# open-usb-can-2021.net
KiCad netlist of a schematic drawn in EAGLE
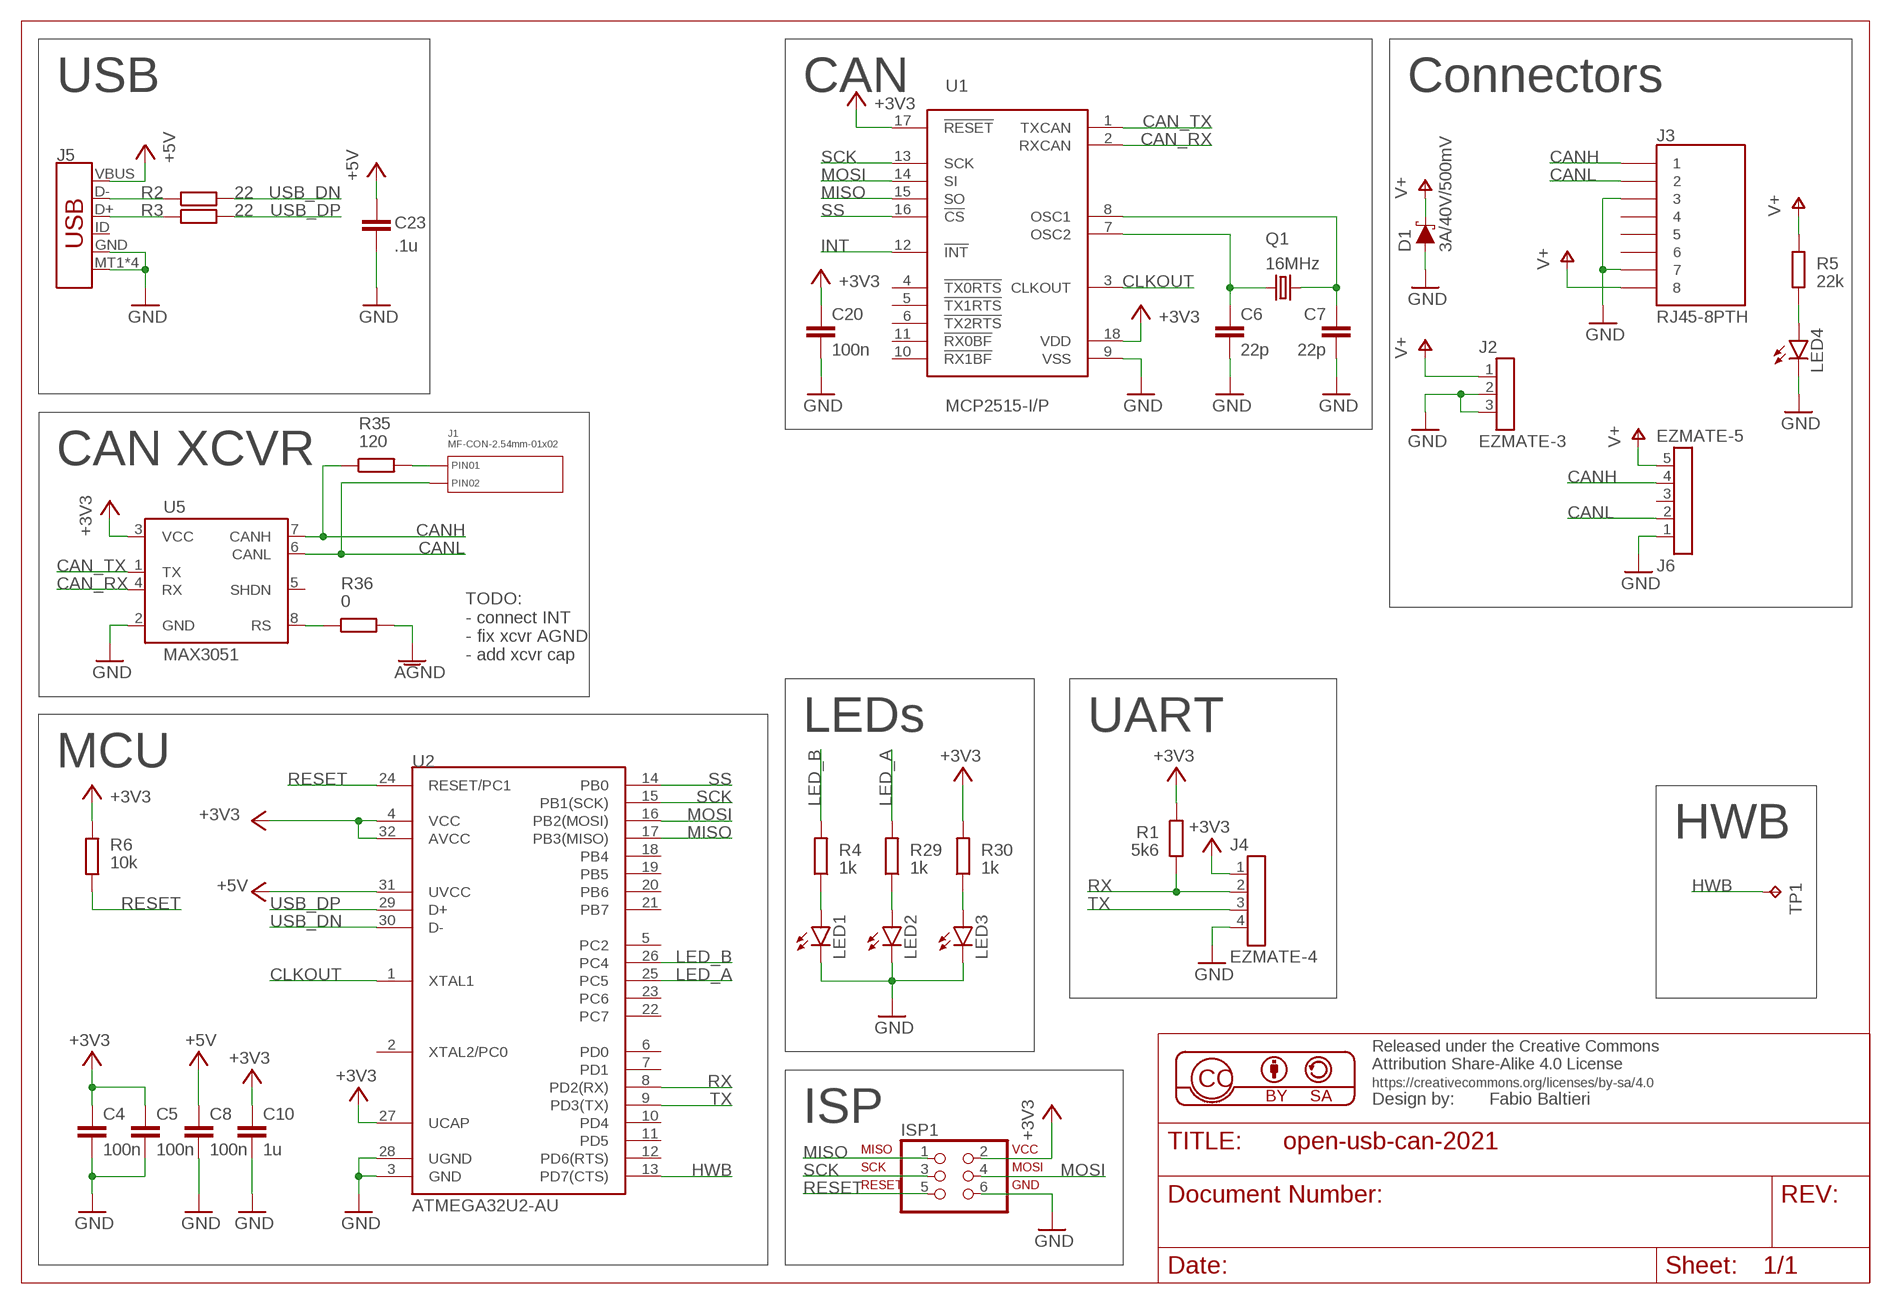
[diagram p0: schematic, sheet 1]

(export (version "E")
  (design (tool "Eeschema 10.0.6"))
  (components
    (comp (ref "C4")
      (value "100n")
      (footprint "eagle-import:0402")
      (libsource (lib "eagle-import") (part "C0402"))
    )
    (comp (ref "C5")
      (value "100n")
      (footprint "eagle-import:0402")
      (libsource (lib "eagle-import") (part "C0402"))
    )
    (comp (ref "C6")
      (value "22p")
      (footprint "eagle-import:C0805")
      (libsource (lib "eagle-import") (part "C-EUC0805"))
    )
    (comp (ref "C7")
      (value "22p")
      (footprint "eagle-import:C0805")
      (libsource (lib "eagle-import") (part "C-EUC0805"))
    )
    (comp (ref "C8")
      (value "100n")
      (footprint "eagle-import:0402")
      (libsource (lib "eagle-import") (part "C0402"))
    )
    (comp (ref "C10")
      (value "1u")
      (footprint "eagle-import:0603")
      (libsource (lib "eagle-import") (part "C0603"))
    )
    (comp (ref "C20")
      (value "100n")
      (footprint "eagle-import:0402")
      (libsource (lib "eagle-import") (part "C0402"))
    )
    (comp (ref "C23")
      (value ".1u")
      (footprint "eagle-import:0603")
      (libsource (lib "eagle-import") (part "C0603"))
    )
    (comp (ref "D1")
      (value "3A/40V/500mV")
      (footprint "eagle-import:SMA-DIODE")
      (libsource (lib "eagle-import") (part "DIODE-SCHOTTKY-B340A"))
    )
    (comp (ref "ISP1")
      (value "ISP-AVR910TP")
      (footprint "eagle-import:2X03_TP")
      (libsource (lib "eagle-import") (part "ISP-AVR910TP"))
    )
    (comp (ref "J1")
      (value "MF-CON-2.54mm-01x02")
      (footprint "eagle-import:PTH_2.54MM_01X02")
      (fields (field (name "HOUSEPART") "YES"))
      (libsource (lib "eagle-import") (part "CON_01X02_PTH_2.54MM"))
    )
    (comp (ref "J2")
      (value "EZMATE-3")
      (footprint "eagle-import:EZMATE-3")
      (libsource (lib "eagle-import") (part "EZMATE-3"))
    )
    (comp (ref "J3")
      (value "RJ45-8PTH")
      (footprint "eagle-import:RJ45-8")
      (libsource (lib "eagle-import") (part "RJ45-8PTH"))
    )
    (comp (ref "J4")
      (value "EZMATE-4")
      (footprint "eagle-import:EZMATE-4")
      (libsource (lib "eagle-import") (part "EZMATE-4"))
    )
    (comp (ref "J5")
      (value "USB_MICRO-B_SMT")
      (footprint "eagle-import:USB-MICROB")
      (libsource (lib "eagle-import") (part "USB_MICRO-B_SMT"))
    )
    (comp (ref "J6")
      (value "EZMATE-5")
      (footprint "eagle-import:EZMATE-5")
      (libsource (lib "eagle-import") (part "EZMATE-5"))
    )
    (comp (ref "LED1")
      (value "LEDCHIPLED_0603")
      (footprint "eagle-import:CHIPLED_0603")
      (libsource (lib "eagle-import") (part "LEDCHIPLED_0603"))
    )
    (comp (ref "LED2")
      (value "LEDCHIPLED_0603")
      (footprint "eagle-import:CHIPLED_0603")
      (libsource (lib "eagle-import") (part "LEDCHIPLED_0603"))
    )
    (comp (ref "LED3")
      (value "LEDCHIPLED_0603")
      (footprint "eagle-import:CHIPLED_0603")
      (libsource (lib "eagle-import") (part "LEDCHIPLED_0603"))
    )
    (comp (ref "LED4")
      (value "LEDCHIPLED_0603")
      (footprint "eagle-import:CHIPLED_0603")
      (libsource (lib "eagle-import") (part "LEDCHIPLED_0603"))
    )
    (comp (ref "Q1")
      (value "16MHz")
      (footprint "eagle-import:HC49U-V")
      (libsource (lib "eagle-import") (part "CRYSTALHC49UV"))
    )
    (comp (ref "R1")
      (value "5k6")
      (footprint "eagle-import:0402")
      (libsource (lib "eagle-import") (part "R0402"))
    )
    (comp (ref "R2")
      (value "22")
      (footprint "eagle-import:0603")
      (libsource (lib "eagle-import") (part "R0603"))
    )
    (comp (ref "R3")
      (value "22")
      (footprint "eagle-import:0603")
      (libsource (lib "eagle-import") (part "R0603"))
    )
    (comp (ref "R4")
      (value "1k")
      (footprint "eagle-import:0402")
      (libsource (lib "eagle-import") (part "R0402"))
    )
    (comp (ref "R5")
      (value "22k")
      (footprint "eagle-import:0603")
      (libsource (lib "eagle-import") (part "R0603"))
    )
    (comp (ref "R6")
      (value "10k")
      (footprint "eagle-import:0402")
      (libsource (lib "eagle-import") (part "R0402"))
    )
    (comp (ref "R29")
      (value "1k")
      (footprint "eagle-import:0402")
      (libsource (lib "eagle-import") (part "R0402"))
    )
    (comp (ref "R30")
      (value "1k")
      (footprint "eagle-import:0402")
      (libsource (lib "eagle-import") (part "R0402"))
    )
    (comp (ref "R35")
      (value "120")
      (footprint "eagle-import:R0805")
      (libsource (lib "eagle-import") (part "R-EU_R0805"))
    )
    (comp (ref "R36")
      (value "0")
      (footprint "eagle-import:0603")
      (libsource (lib "eagle-import") (part "R0603"))
    )
    (comp (ref "TP1")
      (value "TPTP08R")
      (footprint "eagle-import:TP08R")
      (libsource (lib "eagle-import") (part "TPTP08R"))
    )
    (comp (ref "U1")
      (value "MCP2515-I/P")
      (footprint "eagle-import:SO-18DW")
      (libsource (lib "eagle-import") (part "MCP2515-I/P"))
    )
    (comp (ref "U2")
      (value "ATMEGA32U2-AU")
      (footprint "eagle-import:TQFP32-08")
      (libsource (lib "eagle-import") (part "ATMEGA8U2AU"))
    )
    (comp (ref "U5")
      (value "MAX3051")
      (footprint "eagle-import:SO08")
      (libsource (lib "eagle-import") (part "MAX3051"))
    )
  )
  (nets
    (net (code "1") (name "+3V3") (class "Default")
      (node (ref "C10") (pin "1") (pinfunction "1_1") (pintype "passive"))
      (node (ref "C20") (pin "1") (pinfunction "1_1") (pintype "passive"))
      (node (ref "C4") (pin "1") (pinfunction "1_1") (pintype "passive"))
      (node (ref "C5") (pin "1") (pinfunction "1_1") (pintype "passive"))
      (node (ref "ISP1") (pin "2") (pinfunction "2_2") (pintype "passive"))
      (node (ref "J4") (pin "1") (pinfunction "P$1_1") (pintype "bidirectional"))
      (node (ref "R1") (pin "1") (pinfunction "1_1") (pintype "passive"))
      (node (ref "R30") (pin "2") (pinfunction "2_2") (pintype "passive"))
      (node (ref "R6") (pin "1") (pinfunction "1_1") (pintype "passive"))
      (node (ref "U1") (pin "17") (pinfunction "~{RESET}_17") (pintype "bidirectional"))
      (node (ref "U1") (pin "18") (pinfunction "VDD_18") (pintype "power_in"))
      (node (ref "U2") (pin "27") (pinfunction "UCAP_27") (pintype "bidirectional"))
      (node (ref "U2") (pin "32") (pinfunction "AVCC_32") (pintype "bidirectional"))
      (node (ref "U2") (pin "4") (pinfunction "VCC_4") (pintype "bidirectional"))
      (node (ref "U5") (pin "3") (pinfunction "VCC_3") (pintype "bidirectional"))
    )
    (net (code "2") (name "+5V") (class "Default")
      (node (ref "C23") (pin "1") (pinfunction "1_1") (pintype "passive"))
      (node (ref "C8") (pin "1") (pinfunction "1_1") (pintype "passive"))
      (node (ref "J5") (pin "VBUS") (pinfunction "VBUS_VBUS") (pintype "power_in"))
      (node (ref "U2") (pin "31") (pinfunction "UVCC_31") (pintype "bidirectional"))
    )
    (net (code "3") (name "/CANH") (class "Default")
      (node (ref "J3") (pin "1") (pinfunction "1_1") (pintype "bidirectional"))
      (node (ref "J6") (pin "4") (pinfunction "P$4_4") (pintype "bidirectional"))
      (node (ref "R35") (pin "1") (pinfunction "1_1") (pintype "passive"))
      (node (ref "U5") (pin "7") (pinfunction "CANH_7") (pintype "bidirectional"))
    )
    (net (code "4") (name "/CANL") (class "Default")
      (node (ref "J1") (pin "P$2") (pinfunction "PIN2_P$2") (pintype "bidirectional"))
      (node (ref "J3") (pin "2") (pinfunction "2_2") (pintype "bidirectional"))
      (node (ref "J6") (pin "2") (pinfunction "P$2_2") (pintype "bidirectional"))
      (node (ref "U5") (pin "6") (pinfunction "CANL_6") (pintype "bidirectional"))
    )
    (net (code "5") (name "/CAN_RX") (class "Default")
      (node (ref "U1") (pin "2") (pinfunction "RXCAN_2") (pintype "bidirectional"))
      (node (ref "U5") (pin "4") (pinfunction "RX_4") (pintype "bidirectional"))
    )
    (net (code "6") (name "/CAN_TX") (class "Default")
      (node (ref "U1") (pin "1") (pinfunction "TXCAN_1") (pintype "bidirectional"))
      (node (ref "U5") (pin "1") (pinfunction "TX_1") (pintype "bidirectional"))
    )
    (net (code "7") (name "/CLKOUT") (class "Default")
      (node (ref "U1") (pin "3") (pinfunction "CLKOUT_3") (pintype "bidirectional"))
      (node (ref "U2") (pin "1") (pinfunction "XTAL1_1") (pintype "bidirectional"))
    )
    (net (code "8") (name "/HWB") (class "Default")
      (node (ref "TP1") (pin "TP") (pinfunction "TP_TP") (pintype "input"))
      (node (ref "U2") (pin "13") (pinfunction "PD7(CTS)_13") (pintype "bidirectional"))
    )
    (net (code "9") (name "/INT") (class "Default")
      (node (ref "U1") (pin "12") (pinfunction "~{INT}_12") (pintype "bidirectional"))
    )
    (net (code "10") (name "/LED_A") (class "Default")
      (node (ref "R29") (pin "2") (pinfunction "2_2") (pintype "passive"))
      (node (ref "U2") (pin "25") (pinfunction "PC5_25") (pintype "bidirectional"))
    )
    (net (code "11") (name "/LED_B") (class "Default")
      (node (ref "R4") (pin "2") (pinfunction "2_2") (pintype "passive"))
      (node (ref "U2") (pin "26") (pinfunction "PC4_26") (pintype "bidirectional"))
    )
    (net (code "12") (name "/MISO") (class "Default")
      (node (ref "ISP1") (pin "1") (pinfunction "1_1") (pintype "passive"))
      (node (ref "U1") (pin "15") (pinfunction "SO_15") (pintype "bidirectional"))
      (node (ref "U2") (pin "17") (pinfunction "PB3(MISO)_17") (pintype "bidirectional"))
    )
    (net (code "13") (name "/MOSI") (class "Default")
      (node (ref "ISP1") (pin "4") (pinfunction "4_4") (pintype "passive"))
      (node (ref "U1") (pin "14") (pinfunction "SI_14") (pintype "bidirectional"))
      (node (ref "U2") (pin "16") (pinfunction "PB2(MOSI)_16") (pintype "bidirectional"))
    )
    (net (code "14") (name "/RESET") (class "Default")
      (node (ref "ISP1") (pin "5") (pinfunction "5_5") (pintype "passive"))
      (node (ref "R6") (pin "2") (pinfunction "2_2") (pintype "passive"))
      (node (ref "U2") (pin "24") (pinfunction "RESET/PC1_24") (pintype "bidirectional"))
    )
    (net (code "15") (name "/RX") (class "Default")
      (node (ref "J4") (pin "2") (pinfunction "P$2_2") (pintype "bidirectional"))
      (node (ref "R1") (pin "2") (pinfunction "2_2") (pintype "passive"))
      (node (ref "U2") (pin "8") (pinfunction "PD2(RX)_8") (pintype "bidirectional"))
    )
    (net (code "16") (name "/SCK") (class "Default")
      (node (ref "ISP1") (pin "3") (pinfunction "3_3") (pintype "passive"))
      (node (ref "U1") (pin "13") (pinfunction "SCK_13") (pintype "bidirectional"))
      (node (ref "U2") (pin "15") (pinfunction "PB1(SCK)_15") (pintype "bidirectional"))
    )
    (net (code "17") (name "/SS") (class "Default")
      (node (ref "U1") (pin "16") (pinfunction "~{CS}_16") (pintype "bidirectional"))
      (node (ref "U2") (pin "14") (pinfunction "PB0_14") (pintype "bidirectional"))
    )
    (net (code "18") (name "/TX") (class "Default")
      (node (ref "J4") (pin "3") (pinfunction "P$3_3") (pintype "bidirectional"))
      (node (ref "U2") (pin "9") (pinfunction "PD3(TX)_9") (pintype "bidirectional"))
    )
    (net (code "19") (name "/USB_DN") (class "Default")
      (node (ref "R2") (pin "2") (pinfunction "2_2") (pintype "passive"))
      (node (ref "U2") (pin "30") (pinfunction "D-_30") (pintype "bidirectional"))
    )
    (net (code "20") (name "/USB_DP") (class "Default")
      (node (ref "R3") (pin "2") (pinfunction "2_2") (pintype "passive"))
      (node (ref "U2") (pin "29") (pinfunction "D+_29") (pintype "bidirectional"))
    )
    (net (code "21") (name "AGND") (class "Default")
      (node (ref "R36") (pin "2") (pinfunction "2_2") (pintype "passive"))
    )
    (net (code "22") (name "GND") (class "Default")
      (node (ref "C10") (pin "2") (pinfunction "2_2") (pintype "passive"))
      (node (ref "C20") (pin "2") (pinfunction "2_2") (pintype "passive"))
      (node (ref "C23") (pin "2") (pinfunction "2_2") (pintype "passive"))
      (node (ref "C4") (pin "2") (pinfunction "2_2") (pintype "passive"))
      (node (ref "C5") (pin "2") (pinfunction "2_2") (pintype "passive"))
      (node (ref "C6") (pin "2") (pinfunction "2_2") (pintype "passive"))
      (node (ref "C7") (pin "2") (pinfunction "2_2") (pintype "passive"))
      (node (ref "C8") (pin "2") (pinfunction "2_2") (pintype "passive"))
      (node (ref "D1") (pin "A") (pinfunction "A_A") (pintype "passive"))
      (node (ref "ISP1") (pin "6") (pinfunction "6_6") (pintype "passive"))
      (node (ref "J2") (pin "2") (pinfunction "P$2_2") (pintype "bidirectional"))
      (node (ref "J2") (pin "3") (pinfunction "P$3_3") (pintype "bidirectional"))
      (node (ref "J3") (pin "3") (pinfunction "3_3") (pintype "bidirectional"))
      (node (ref "J3") (pin "7") (pinfunction "7_7") (pintype "bidirectional"))
      (node (ref "J4") (pin "4") (pinfunction "P$4_4") (pintype "bidirectional"))
      (node (ref "J5") (pin "GND") (pinfunction "GND_GND") (pintype "power_in"))
      (node (ref "J5") (pin "MT1") (pinfunction "SHIELD_MT1") (pintype "bidirectional"))
      (node (ref "J5") (pin "MT2") (pinfunction "SHIELD_MT2") (pintype "bidirectional"))
      (node (ref "J5") (pin "P$1") (pinfunction "SHIELD_P$1") (pintype "bidirectional"))
      (node (ref "J5") (pin "P$2") (pinfunction "SHIELD_P$2") (pintype "bidirectional"))
      (node (ref "J6") (pin "1") (pinfunction "P$1_1") (pintype "bidirectional"))
      (node (ref "LED1") (pin "C") (pinfunction "C_C") (pintype "passive"))
      (node (ref "LED2") (pin "C") (pinfunction "C_C") (pintype "passive"))
      (node (ref "LED3") (pin "C") (pinfunction "C_C") (pintype "passive"))
      (node (ref "LED4") (pin "C") (pinfunction "C_C") (pintype "passive"))
      (node (ref "U1") (pin "9") (pinfunction "VSS_9") (pintype "power_in"))
      (node (ref "U2") (pin "28") (pinfunction "UGND_28") (pintype "bidirectional"))
      (node (ref "U2") (pin "3") (pinfunction "GND_3") (pintype "bidirectional"))
      (node (ref "U5") (pin "2") (pinfunction "GND_2") (pintype "bidirectional"))
    )
    (net (code "23") (name "Net-(J1-PIN1)") (class "Default")
      (node (ref "J1") (pin "P$1") (pinfunction "PIN1_P$1") (pintype "bidirectional"))
      (node (ref "R35") (pin "2") (pinfunction "2_2") (pintype "passive"))
    )
    (net (code "24") (name "Net-(J5-PadD+)") (class "Default")
      (node (ref "J5") (pin "D+") (pinfunction "D+_D+") (pintype "bidirectional"))
      (node (ref "R3") (pin "1") (pinfunction "1_1") (pintype "passive"))
    )
    (net (code "25") (name "Net-(J5-PadD-)") (class "Default")
      (node (ref "J5") (pin "D-") (pinfunction "D-_D-") (pintype "bidirectional"))
      (node (ref "R2") (pin "1") (pinfunction "1_1") (pintype "passive"))
    )
    (net (code "26") (name "Net-(LED1-PadA)") (class "Default")
      (node (ref "LED1") (pin "A") (pinfunction "A_A") (pintype "passive"))
      (node (ref "R4") (pin "1") (pinfunction "1_1") (pintype "passive"))
    )
    (net (code "27") (name "Net-(LED2-PadA)") (class "Default")
      (node (ref "LED2") (pin "A") (pinfunction "A_A") (pintype "passive"))
      (node (ref "R29") (pin "1") (pinfunction "1_1") (pintype "passive"))
    )
    (net (code "28") (name "Net-(LED3-PadA)") (class "Default")
      (node (ref "LED3") (pin "A") (pinfunction "A_A") (pintype "passive"))
      (node (ref "R30") (pin "1") (pinfunction "1_1") (pintype "passive"))
    )
    (net (code "29") (name "Net-(LED4-PadA)") (class "Default")
      (node (ref "LED4") (pin "A") (pinfunction "A_A") (pintype "passive"))
      (node (ref "R5") (pin "1") (pinfunction "1_1") (pintype "passive"))
    )
    (net (code "30") (name "Net-(U1-OSC1)") (class "Default")
      (node (ref "C7") (pin "1") (pinfunction "1_1") (pintype "passive"))
      (node (ref "Q1") (pin "2") (pinfunction "2_2") (pintype "passive"))
      (node (ref "U1") (pin "8") (pinfunction "OSC1_8") (pintype "bidirectional"))
    )
    (net (code "31") (name "Net-(U1-OSC2)") (class "Default")
      (node (ref "C6") (pin "1") (pinfunction "1_1") (pintype "passive"))
      (node (ref "Q1") (pin "1") (pinfunction "1_1") (pintype "passive"))
      (node (ref "U1") (pin "7") (pinfunction "OSC2_7") (pintype "bidirectional"))
    )
    (net (code "32") (name "Net-(U5-RS)") (class "Default")
      (node (ref "R36") (pin "1") (pinfunction "1_1") (pintype "passive"))
      (node (ref "U5") (pin "8") (pinfunction "RS_8") (pintype "bidirectional"))
    )
    (net (code "33") (name "V+") (class "Default")
      (node (ref "D1") (pin "C") (pinfunction "C_C") (pintype "passive"))
      (node (ref "J2") (pin "1") (pinfunction "P$1_1") (pintype "bidirectional"))
      (node (ref "J3") (pin "8") (pinfunction "8_8") (pintype "bidirectional"))
      (node (ref "J6") (pin "5") (pinfunction "P$5_5") (pintype "bidirectional"))
      (node (ref "R5") (pin "2") (pinfunction "2_2") (pintype "passive"))
    )
    (net (code "34") (name "unconnected-(J3-Pad4)") (class "Default")
      (node (ref "J3") (pin "4") (pinfunction "4_4") (pintype "bidirectional"))
    )
    (net (code "35") (name "unconnected-(J3-Pad5)") (class "Default")
      (node (ref "J3") (pin "5") (pinfunction "5_5") (pintype "bidirectional"))
    )
    (net (code "36") (name "unconnected-(J3-Pad6)") (class "Default")
      (node (ref "J3") (pin "6") (pinfunction "6_6") (pintype "bidirectional"))
    )
    (net (code "37") (name "unconnected-(J5-PadID)") (class "Default")
      (node (ref "J5") (pin "ID") (pinfunction "ID_ID") (pintype "bidirectional"))
    )
    (net (code "38") (name "unconnected-(J6-P$3-Pad3)") (class "Default")
      (node (ref "J6") (pin "3") (pinfunction "P$3_3") (pintype "bidirectional"))
    )
    (net (code "39") (name "unconnected-(U1-~{RX0BF}-Pad11)") (class "Default")
      (node (ref "U1") (pin "11") (pinfunction "~{RX0BF}_11") (pintype "bidirectional"))
    )
    (net (code "40") (name "unconnected-(U1-~{RX1BF}-Pad10)") (class "Default")
      (node (ref "U1") (pin "10") (pinfunction "~{RX1BF}_10") (pintype "bidirectional"))
    )
    (net (code "41") (name "unconnected-(U1-~{TX0RTS}-Pad4)") (class "Default")
      (node (ref "U1") (pin "4") (pinfunction "~{TX0RTS}_4") (pintype "bidirectional"))
    )
    (net (code "42") (name "unconnected-(U1-~{TX1RTS}-Pad5)") (class "Default")
      (node (ref "U1") (pin "5") (pinfunction "~{TX1RTS}_5") (pintype "bidirectional"))
    )
    (net (code "43") (name "unconnected-(U1-~{TX2RTS}-Pad6)") (class "Default")
      (node (ref "U1") (pin "6") (pinfunction "~{TX2RTS}_6") (pintype "bidirectional"))
    )
    (net (code "44") (name "unconnected-(U2-PB4-Pad18)") (class "Default")
      (node (ref "U2") (pin "18") (pinfunction "PB4_18") (pintype "bidirectional"))
    )
    (net (code "45") (name "unconnected-(U2-PB5-Pad19)") (class "Default")
      (node (ref "U2") (pin "19") (pinfunction "PB5_19") (pintype "bidirectional"))
    )
    (net (code "46") (name "unconnected-(U2-PB6-Pad20)") (class "Default")
      (node (ref "U2") (pin "20") (pinfunction "PB6_20") (pintype "bidirectional"))
    )
    (net (code "47") (name "unconnected-(U2-PB7-Pad21)") (class "Default")
      (node (ref "U2") (pin "21") (pinfunction "PB7_21") (pintype "bidirectional"))
    )
    (net (code "48") (name "unconnected-(U2-PC2-Pad5)") (class "Default")
      (node (ref "U2") (pin "5") (pinfunction "PC2_5") (pintype "bidirectional"))
    )
    (net (code "49") (name "unconnected-(U2-PC6-Pad23)") (class "Default")
      (node (ref "U2") (pin "23") (pinfunction "PC6_23") (pintype "bidirectional"))
    )
    (net (code "50") (name "unconnected-(U2-PC7-Pad22)") (class "Default")
      (node (ref "U2") (pin "22") (pinfunction "PC7_22") (pintype "bidirectional"))
    )
    (net (code "51") (name "unconnected-(U2-PD0-Pad6)") (class "Default")
      (node (ref "U2") (pin "6") (pinfunction "PD0_6") (pintype "bidirectional"))
    )
    (net (code "52") (name "unconnected-(U2-PD1-Pad7)") (class "Default")
      (node (ref "U2") (pin "7") (pinfunction "PD1_7") (pintype "bidirectional"))
    )
    (net (code "53") (name "unconnected-(U2-PD4-Pad10)") (class "Default")
      (node (ref "U2") (pin "10") (pinfunction "PD4_10") (pintype "bidirectional"))
    )
    (net (code "54") (name "unconnected-(U2-PD5-Pad11)") (class "Default")
      (node (ref "U2") (pin "11") (pinfunction "PD5_11") (pintype "bidirectional"))
    )
    (net (code "55") (name "unconnected-(U2-PD6(RTS)-Pad12)") (class "Default")
      (node (ref "U2") (pin "12") (pinfunction "PD6(RTS)_12") (pintype "bidirectional"))
    )
    (net (code "56") (name "unconnected-(U2-XTAL2{slash}PC0-Pad2)") (class "Default")
      (node (ref "U2") (pin "2") (pinfunction "XTAL2/PC0_2") (pintype "bidirectional"))
    )
    (net (code "57") (name "unconnected-(U5-SHDN-Pad5)") (class "Default")
      (node (ref "U5") (pin "5") (pinfunction "SHDN_5") (pintype "bidirectional"))
    )
  )
)
